# LEDDimmerDuo.net
KiCad netlist of a schematic drawn in EAGLE
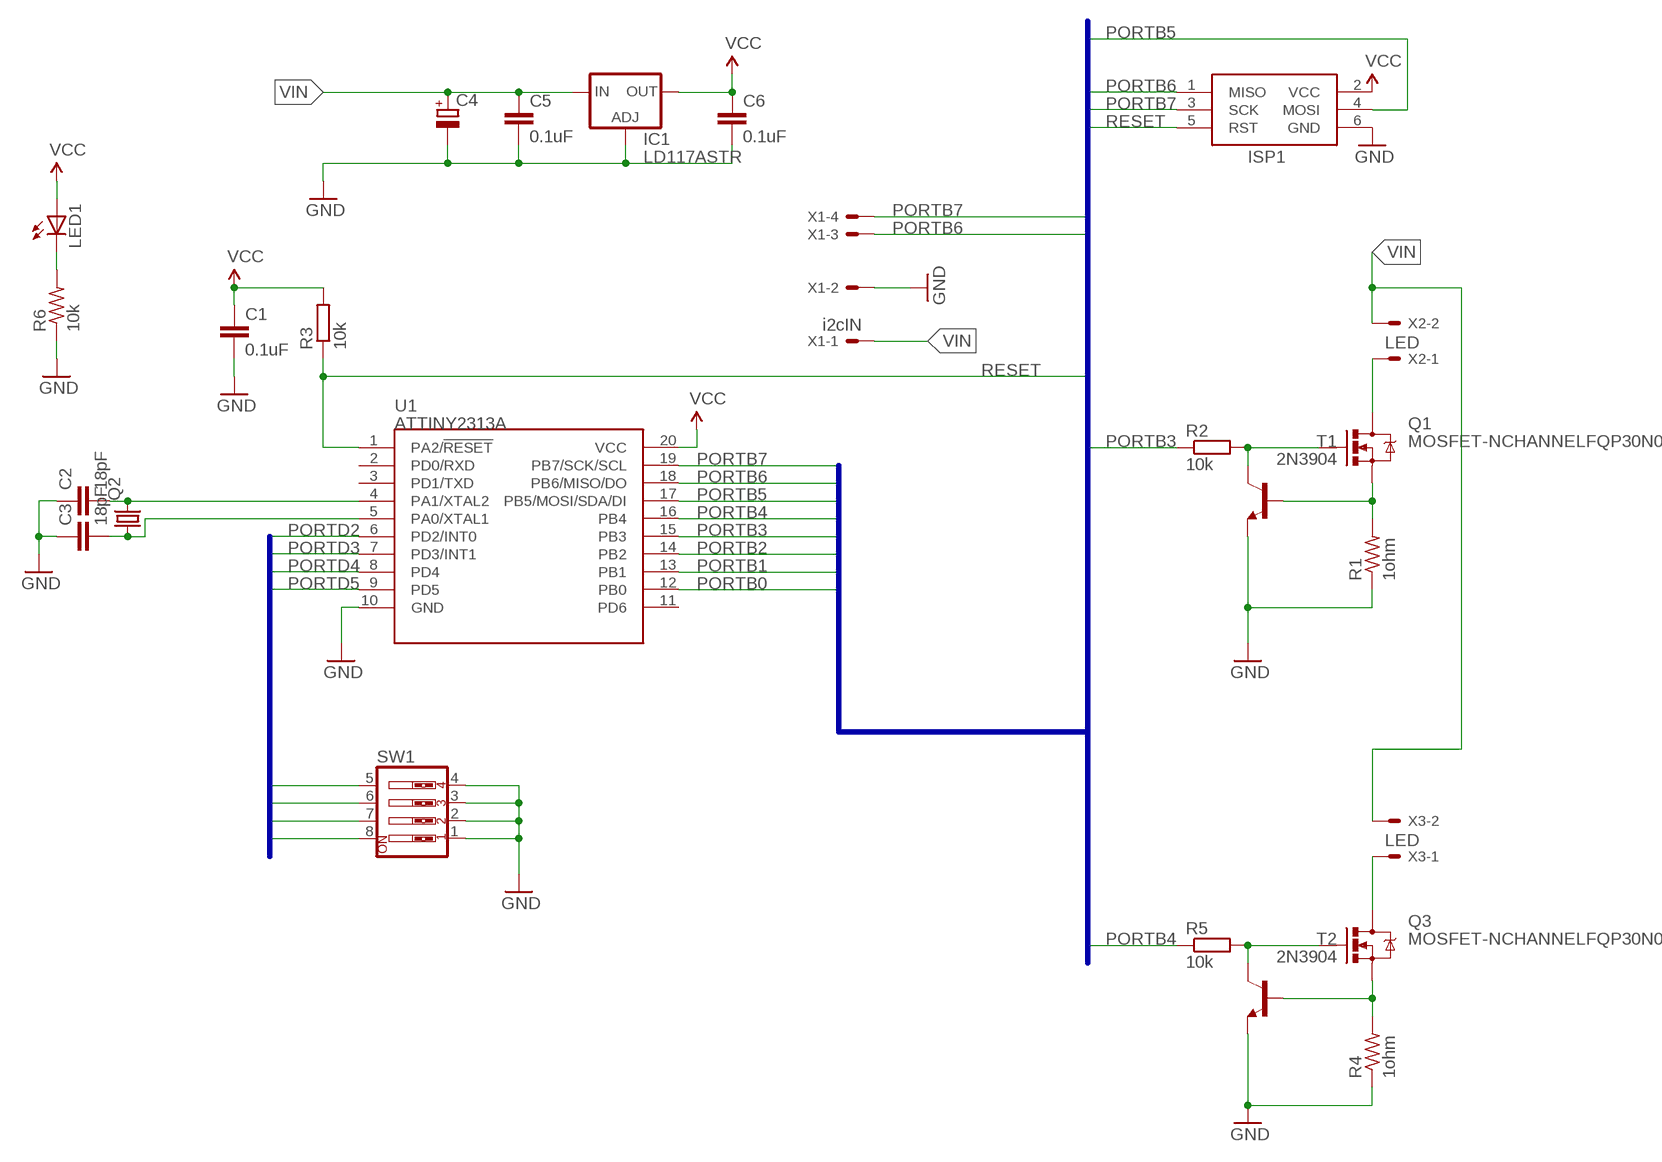
[diagram p0: schematic, sheet 1]

(export (version "E")
  (design (tool "Eeschema 10.0.6"))
  (components
    (comp (ref "C1")
      (value "0.1uF")
      (footprint "eagle-import:0805")
      (libsource (lib "eagle-import") (part "CAP0805"))
    )
    (comp (ref "C2")
      (value "18pF")
      (footprint "eagle-import:0805")
      (libsource (lib "eagle-import") (part "CAP0805"))
    )
    (comp (ref "C3")
      (value "18pF")
      (footprint "eagle-import:0805")
      (libsource (lib "eagle-import") (part "CAP0805"))
    )
    (comp (ref "C4")
      (value "CPOL-EUE3.5-10")
      (footprint "eagle-import:E3,5-10")
      (libsource (lib "eagle-import") (part "CPOL-EUE3.5-10"))
    )
    (comp (ref "C5")
      (value "0.1uF")
      (footprint "eagle-import:0805")
      (libsource (lib "eagle-import") (part "CAP0805"))
    )
    (comp (ref "C6")
      (value "0.1uF")
      (footprint "eagle-import:0805")
      (libsource (lib "eagle-import") (part "CAP0805"))
    )
    (comp (ref "IC1")
      (value "LD117ASTR")
      (footprint "eagle-import:SOT223")
      (libsource (lib "eagle-import") (part "LD117A?STR"))
    )
    (comp (ref "ISP1")
      (value "AVRISP-6")
      (footprint "eagle-import:AVRISP")
      (libsource (lib "eagle-import") (part "AVRISP-6"))
    )
    (comp (ref "LED1")
      (value "LED0603")
      (footprint "eagle-import:LED-0603")
      (libsource (lib "eagle-import") (part "LED0603"))
    )
    (comp (ref "Q1")
      (value "MOSFET-NCHANNELFQP30N06L")
      (footprint "eagle-import:TO220V")
      (libsource (lib "eagle-import") (part "MOSFET-NCHANNELFQP30N06L"))
    )
    (comp (ref "Q2")
      (value "CRYSTALSM49")
      (footprint "eagle-import:SM49")
      (libsource (lib "eagle-import") (part "CRYSTALSM49"))
    )
    (comp (ref "Q3")
      (value "MOSFET-NCHANNELFQP30N06L")
      (footprint "eagle-import:TO220V")
      (libsource (lib "eagle-import") (part "MOSFET-NCHANNELFQP30N06L"))
    )
    (comp (ref "R1")
      (value "1ohm")
      (footprint "eagle-import:VTA54")
      (libsource (lib "eagle-import") (part "R-US_VTA54"))
    )
    (comp (ref "R2")
      (value "10k")
      (footprint "eagle-import:R0805")
      (libsource (lib "eagle-import") (part "R-EU_R0805"))
    )
    (comp (ref "R3")
      (value "10k")
      (footprint "eagle-import:R0805")
      (libsource (lib "eagle-import") (part "R-EU_R0805"))
    )
    (comp (ref "R4")
      (value "1ohm")
      (footprint "eagle-import:VTA54")
      (libsource (lib "eagle-import") (part "R-US_VTA54"))
    )
    (comp (ref "R5")
      (value "10k")
      (footprint "eagle-import:R0805")
      (libsource (lib "eagle-import") (part "R-EU_R0805"))
    )
    (comp (ref "R6")
      (value "10k")
      (footprint "eagle-import:R0603")
      (libsource (lib "eagle-import") (part "R-US_R0603"))
    )
    (comp (ref "SW1")
      (value "SW_DIP-4")
      (footprint "eagle-import:EDG-04")
      (libsource (lib "eagle-import") (part "SW_DIP-4"))
    )
    (comp (ref "T1")
      (value "2N3904")
      (footprint "eagle-import:TO92")
      (libsource (lib "eagle-import") (part "2N3904"))
    )
    (comp (ref "T2")
      (value "2N3904")
      (footprint "eagle-import:TO92")
      (libsource (lib "eagle-import") (part "2N3904"))
    )
    (comp (ref "U1")
      (value "ATTINY2313A")
      (footprint "eagle-import:SOP20W")
      (libsource (lib "eagle-import") (part "ATTINY2313A"))
    )
    (comp (ref "X1")
      (value "i2cIN")
      (footprint "eagle-import:22-23-2041")
      (fields (field (name "MF") "MOLEX") (field (name "MPN") "22-23-2041"))
      (libsource (lib "eagle-import") (part "22-23-2041"))
    )
    (comp (ref "X2")
      (value "LED")
      (footprint "eagle-import:22-23-2021")
      (fields (field (name "MF") "MOLEX") (field (name "MPN") "22-23-2021"))
      (libsource (lib "eagle-import") (part "22-23-2021"))
    )
    (comp (ref "X3")
      (value "LED")
      (footprint "eagle-import:22-23-2021")
      (fields (field (name "MF") "MOLEX") (field (name "MPN") "22-23-2021"))
      (libsource (lib "eagle-import") (part "22-23-2021"))
    )
  )
  (nets
    (net (code "1") (name "/PORTB0") (class "Default")
      (node (ref "U1") (pin "12") (pinfunction "PB0_12") (pintype "bidirectional"))
    )
    (net (code "2") (name "/PORTB1") (class "Default")
      (node (ref "U1") (pin "13") (pinfunction "PB1_13") (pintype "bidirectional"))
    )
    (net (code "3") (name "/PORTB2") (class "Default")
      (node (ref "U1") (pin "14") (pinfunction "PB2_14") (pintype "bidirectional"))
    )
    (net (code "4") (name "/PORTB3") (class "Default")
      (node (ref "R2") (pin "1") (pinfunction "1_1") (pintype "passive"))
      (node (ref "U1") (pin "15") (pinfunction "PB3_15") (pintype "bidirectional"))
    )
    (net (code "5") (name "/PORTB4") (class "Default")
      (node (ref "R5") (pin "1") (pinfunction "1_1") (pintype "passive"))
      (node (ref "U1") (pin "16") (pinfunction "PB4_16") (pintype "bidirectional"))
    )
    (net (code "6") (name "/PORTB5") (class "Default")
      (node (ref "ISP1") (pin "4") (pinfunction "MOSI_4") (pintype "output"))
      (node (ref "U1") (pin "17") (pinfunction "PB5/MOSI/SDA/DI_17") (pintype "bidirectional"))
    )
    (net (code "7") (name "/PORTB6") (class "Default")
      (node (ref "ISP1") (pin "1") (pinfunction "MISO_1") (pintype "input"))
      (node (ref "U1") (pin "18") (pinfunction "PB6/MISO/DO_18") (pintype "bidirectional"))
      (node (ref "X1") (pin "3") (pinfunction "S_3") (pintype "passive"))
    )
    (net (code "8") (name "/PORTB7") (class "Default")
      (node (ref "ISP1") (pin "3") (pinfunction "SCK_3") (pintype "output"))
      (node (ref "U1") (pin "19") (pinfunction "PB7/SCK/SCL_19") (pintype "bidirectional"))
      (node (ref "X1") (pin "4") (pinfunction "S_4") (pintype "passive"))
    )
    (net (code "9") (name "/PORTD2") (class "Default")
      (node (ref "SW1") (pin "5") (pinfunction "5_5") (pintype "passive"))
      (node (ref "U1") (pin "6") (pinfunction "PD2/INT0_6") (pintype "bidirectional"))
    )
    (net (code "10") (name "/PORTD3") (class "Default")
      (node (ref "SW1") (pin "6") (pinfunction "6_6") (pintype "passive"))
      (node (ref "U1") (pin "7") (pinfunction "PD3/INT1_7") (pintype "bidirectional"))
    )
    (net (code "11") (name "/PORTD4") (class "Default")
      (node (ref "SW1") (pin "7") (pinfunction "7_7") (pintype "passive"))
      (node (ref "U1") (pin "8") (pinfunction "PD4_8") (pintype "bidirectional"))
    )
    (net (code "12") (name "/PORTD5") (class "Default")
      (node (ref "SW1") (pin "8") (pinfunction "8_8") (pintype "passive"))
      (node (ref "U1") (pin "9") (pinfunction "PD5_9") (pintype "bidirectional"))
    )
    (net (code "13") (name "/RESET") (class "Default")
      (node (ref "ISP1") (pin "5") (pinfunction "RST_5") (pintype "output"))
      (node (ref "R3") (pin "1") (pinfunction "1_1") (pintype "passive"))
      (node (ref "U1") (pin "1") (pinfunction "PA2/~{RESET}_1") (pintype "bidirectional"))
    )
    (net (code "14") (name "GND") (class "Default")
      (node (ref "C1") (pin "2") (pinfunction "2_2") (pintype "passive"))
      (node (ref "C2") (pin "1") (pinfunction "1_1") (pintype "passive"))
      (node (ref "C3") (pin "1") (pinfunction "1_1") (pintype "passive"))
      (node (ref "C4") (pin "-") (pinfunction "-_-") (pintype "passive"))
      (node (ref "C5") (pin "2") (pinfunction "2_2") (pintype "passive"))
      (node (ref "C6") (pin "2") (pinfunction "2_2") (pintype "passive"))
      (node (ref "IC1") (pin "1") (pinfunction "ADJ_1") (pintype "input"))
      (node (ref "ISP1") (pin "6") (pinfunction "GND_6") (pintype "power_in"))
      (node (ref "R1") (pin "1") (pinfunction "1_1") (pintype "passive"))
      (node (ref "R4") (pin "1") (pinfunction "1_1") (pintype "passive"))
      (node (ref "R6") (pin "1") (pinfunction "1_1") (pintype "passive"))
      (node (ref "SW1") (pin "1") (pinfunction "1_1") (pintype "passive"))
      (node (ref "SW1") (pin "2") (pinfunction "2_2") (pintype "passive"))
      (node (ref "SW1") (pin "3") (pinfunction "3_3") (pintype "passive"))
      (node (ref "SW1") (pin "4") (pinfunction "4_4") (pintype "passive"))
      (node (ref "T1") (pin "3") (pinfunction "E_3") (pintype "passive"))
      (node (ref "T2") (pin "3") (pinfunction "E_3") (pintype "passive"))
      (node (ref "U1") (pin "10") (pinfunction "GND_10") (pintype "bidirectional"))
      (node (ref "X1") (pin "2") (pinfunction "S_2") (pintype "passive"))
    )
    (net (code "15") (name "Net-(LED1-PadC)") (class "Default")
      (node (ref "LED1") (pin "C") (pinfunction "C_C") (pintype "passive"))
      (node (ref "R6") (pin "2") (pinfunction "2_2") (pintype "passive"))
    )
    (net (code "16") (name "Net-(Q1-D)") (class "Default")
      (node (ref "Q1") (pin "2") (pinfunction "D_2") (pintype "passive"))
      (node (ref "X2") (pin "1") (pinfunction "S_1") (pintype "passive"))
    )
    (net (code "17") (name "Net-(Q1-G)") (class "Default")
      (node (ref "Q1") (pin "1") (pinfunction "G_1") (pintype "passive"))
      (node (ref "R2") (pin "2") (pinfunction "2_2") (pintype "passive"))
      (node (ref "T1") (pin "1") (pinfunction "C_1") (pintype "passive"))
    )
    (net (code "18") (name "Net-(Q1-S)") (class "Default")
      (node (ref "Q1") (pin "3") (pinfunction "S_3") (pintype "passive"))
      (node (ref "R1") (pin "2") (pinfunction "2_2") (pintype "passive"))
      (node (ref "T1") (pin "2") (pinfunction "B_2") (pintype "passive"))
    )
    (net (code "19") (name "Net-(Q3-D)") (class "Default")
      (node (ref "Q3") (pin "2") (pinfunction "D_2") (pintype "passive"))
      (node (ref "X3") (pin "1") (pinfunction "S_1") (pintype "passive"))
    )
    (net (code "20") (name "Net-(Q3-G)") (class "Default")
      (node (ref "Q3") (pin "1") (pinfunction "G_1") (pintype "passive"))
      (node (ref "R5") (pin "2") (pinfunction "2_2") (pintype "passive"))
      (node (ref "T2") (pin "1") (pinfunction "C_1") (pintype "passive"))
    )
    (net (code "21") (name "Net-(Q3-S)") (class "Default")
      (node (ref "Q3") (pin "3") (pinfunction "S_3") (pintype "passive"))
      (node (ref "R4") (pin "2") (pinfunction "2_2") (pintype "passive"))
      (node (ref "T2") (pin "2") (pinfunction "B_2") (pintype "passive"))
    )
    (net (code "22") (name "Net-(U1-PA0{slash}XTAL1)") (class "Default")
      (node (ref "C3") (pin "2") (pinfunction "2_2") (pintype "passive"))
      (node (ref "Q2") (pin "1") (pinfunction "1_1") (pintype "passive"))
      (node (ref "U1") (pin "5") (pinfunction "PA0/XTAL1_5") (pintype "bidirectional"))
    )
    (net (code "23") (name "Net-(U1-PA1{slash}XTAL2)") (class "Default")
      (node (ref "C2") (pin "2") (pinfunction "2_2") (pintype "passive"))
      (node (ref "Q2") (pin "2") (pinfunction "2_2") (pintype "passive"))
      (node (ref "U1") (pin "4") (pinfunction "PA1/XTAL2_4") (pintype "bidirectional"))
    )
    (net (code "24") (name "VCC") (class "Default")
      (node (ref "C1") (pin "1") (pinfunction "1_1") (pintype "passive"))
      (node (ref "C6") (pin "1") (pinfunction "1_1") (pintype "passive"))
      (node (ref "IC1") (pin "4") (pinfunction "OUT_4") (pintype "passive"))
      (node (ref "ISP1") (pin "2") (pinfunction "VCC_2") (pintype "power_in"))
      (node (ref "LED1") (pin "A") (pinfunction "A_A") (pintype "passive"))
      (node (ref "R3") (pin "2") (pinfunction "2_2") (pintype "passive"))
      (node (ref "U1") (pin "20") (pinfunction "VCC_20") (pintype "bidirectional"))
    )
    (net (code "25") (name "VIN") (class "Default")
      (node (ref "C4") (pin "+") (pinfunction "+_+") (pintype "passive"))
      (node (ref "C5") (pin "1") (pinfunction "1_1") (pintype "passive"))
      (node (ref "IC1") (pin "3") (pinfunction "IN_3") (pintype "input"))
      (node (ref "X1") (pin "1") (pinfunction "S_1") (pintype "passive"))
      (node (ref "X2") (pin "2") (pinfunction "S_2") (pintype "passive"))
      (node (ref "X3") (pin "2") (pinfunction "S_2") (pintype "passive"))
    )
    (net (code "26") (name "unconnected-(U1-PD0{slash}RXD-Pad2)") (class "Default")
      (node (ref "U1") (pin "2") (pinfunction "PD0/RXD_2") (pintype "bidirectional"))
    )
    (net (code "27") (name "unconnected-(U1-PD1{slash}TXD-Pad3)") (class "Default")
      (node (ref "U1") (pin "3") (pinfunction "PD1/TXD_3") (pintype "bidirectional"))
    )
    (net (code "28") (name "unconnected-(U1-PD6-Pad11)") (class "Default")
      (node (ref "U1") (pin "11") (pinfunction "PD6_11") (pintype "bidirectional"))
    )
  )
)
